# Frame2TTL_v2_1_1.net
KiCad netlist of a schematic drawn in EAGLE
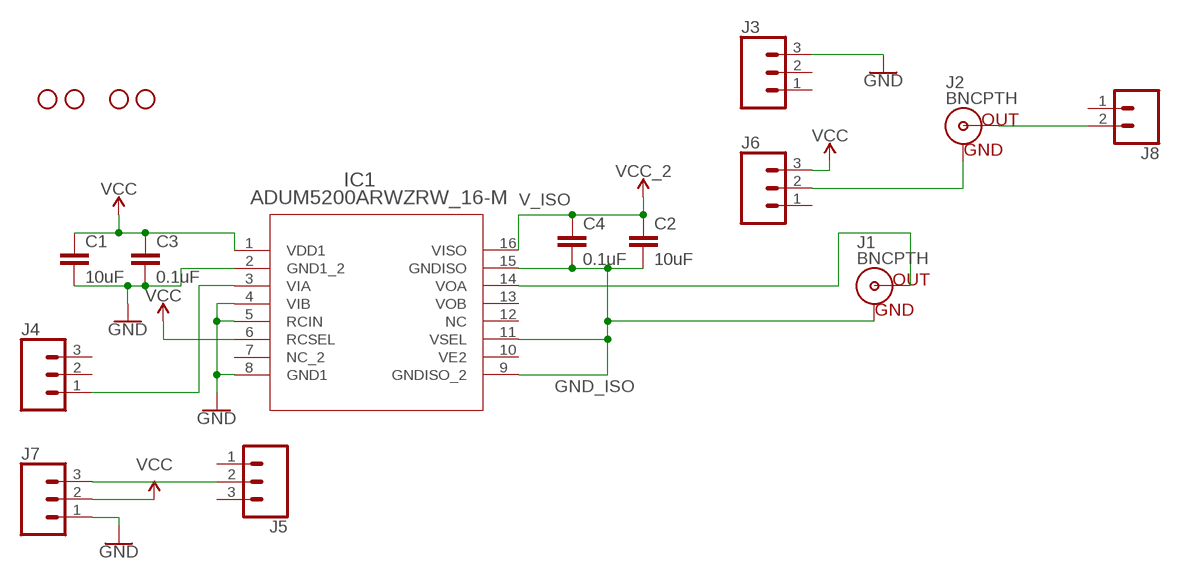
[diagram p0: schematic, sheet 1]

(export (version "E")
  (design (tool "Eeschema 10.0.6"))
  (components
    (comp (ref "C1")
      (value "10uF")
      (footprint "eagle-import:1206")
      (libsource (lib "eagle-import") (part "10UF-1206-6.3V-20%"))
    )
    (comp (ref "C2")
      (value "10uF")
      (footprint "eagle-import:1206")
      (libsource (lib "eagle-import") (part "10UF-1206-6.3V-20%"))
    )
    (comp (ref "C3")
      (value "0.1uF")
      (footprint "eagle-import:0805")
      (libsource (lib "eagle-import") (part "10UF-0805-10V-10%"))
    )
    (comp (ref "C4")
      (value "0.1uF")
      (footprint "eagle-import:0805")
      (libsource (lib "eagle-import") (part "10UF-0805-10V-10%"))
    )
    (comp (ref "H1")
      (value "STAND-OFF")
      (footprint "eagle-import:STAND-OFF")
      (libsource (lib "eagle-import") (part "STAND-OFF"))
    )
    (comp (ref "H2")
      (value "STAND-OFF")
      (footprint "eagle-import:STAND-OFF")
      (libsource (lib "eagle-import") (part "STAND-OFF"))
    )
    (comp (ref "H3")
      (value "STAND-OFF")
      (footprint "eagle-import:STAND-OFF")
      (libsource (lib "eagle-import") (part "STAND-OFF"))
    )
    (comp (ref "H4")
      (value "STAND-OFF")
      (footprint "eagle-import:STAND-OFF")
      (libsource (lib "eagle-import") (part "STAND-OFF"))
    )
    (comp (ref "IC1")
      (value "ADUM5200ARWZRW_16-M")
      (footprint "eagle-import:RW_16-M")
      (libsource (lib "eagle-import") (part "ADUM5200ARWZRW_16-M"))
    )
    (comp (ref "J1")
      (value "BNCPTH")
      (footprint "eagle-import:BNC")
      (libsource (lib "eagle-import") (part "BNCPTH"))
    )
    (comp (ref "J2")
      (value "BNCPTH")
      (footprint "eagle-import:BNC")
      (libsource (lib "eagle-import") (part "BNCPTH"))
    )
    (comp (ref "J3")
      (value "CONN_03LOCK")
      (footprint "eagle-import:1X03_LOCK")
      (libsource (lib "eagle-import") (part "CONN_03LOCK"))
    )
    (comp (ref "J4")
      (value "CONN_03LOCK")
      (footprint "eagle-import:1X03_LOCK")
      (libsource (lib "eagle-import") (part "CONN_03LOCK"))
    )
    (comp (ref "J5")
      (value "CONN_03LOCK")
      (footprint "eagle-import:1X03_LOCK")
      (libsource (lib "eagle-import") (part "CONN_03LOCK"))
    )
    (comp (ref "J6")
      (value "CONN_03LOCK")
      (footprint "eagle-import:1X03_LOCK")
      (libsource (lib "eagle-import") (part "CONN_03LOCK"))
    )
    (comp (ref "J7")
      (value "CONN_03LOCK")
      (footprint "eagle-import:1X03_LOCK")
      (libsource (lib "eagle-import") (part "CONN_03LOCK"))
    )
    (comp (ref "J8")
      (value "CONN_02")
      (footprint "eagle-import:1X02")
      (libsource (lib "eagle-import") (part "CONN_02"))
    )
  )
  (nets
    (net (code "1") (name "/GND_ISO") (class "Default")
      (node (ref "C2") (pin "2") (pinfunction "2_2") (pintype "passive"))
      (node (ref "C4") (pin "2") (pinfunction "2_2") (pintype "passive"))
      (node (ref "IC1") (pin "11") (pinfunction "VSEL_11") (pintype "passive"))
      (node (ref "IC1") (pin "15") (pinfunction "GNDISO_15") (pintype "passive"))
      (node (ref "IC1") (pin "9") (pinfunction "GNDISO_2_9") (pintype "passive"))
      (node (ref "J1") (pin "GND") (pinfunction "GND_GND") (pintype "bidirectional"))
    )
    (net (code "2") (name "GND") (class "Default")
      (node (ref "C1") (pin "2") (pinfunction "2_2") (pintype "passive"))
      (node (ref "C3") (pin "2") (pinfunction "2_2") (pintype "passive"))
      (node (ref "IC1") (pin "2") (pinfunction "GND1_2_2") (pintype "passive"))
      (node (ref "IC1") (pin "4") (pinfunction "VIB_4") (pintype "passive"))
      (node (ref "IC1") (pin "5") (pinfunction "RCIN_5") (pintype "passive"))
      (node (ref "IC1") (pin "8") (pinfunction "GND1_8") (pintype "passive"))
      (node (ref "J3") (pin "3") (pinfunction "3_3") (pintype "passive"))
      (node (ref "J7") (pin "1") (pinfunction "1_1") (pintype "passive"))
    )
    (net (code "3") (name "Net-(IC1-VIA)") (class "Default")
      (node (ref "IC1") (pin "3") (pinfunction "VIA_3") (pintype "passive"))
      (node (ref "J4") (pin "1") (pinfunction "1_1") (pintype "passive"))
    )
    (net (code "4") (name "Net-(IC1-VOA)") (class "Default")
      (node (ref "IC1") (pin "14") (pinfunction "VOA_14") (pintype "passive"))
      (node (ref "J1") (pin "S") (pinfunction "OUT_S") (pintype "bidirectional"))
    )
    (net (code "5") (name "Net-(J2-OUT)") (class "Default")
      (node (ref "J2") (pin "S") (pinfunction "OUT_S") (pintype "bidirectional"))
      (node (ref "J8") (pin "2") (pinfunction "2_2") (pintype "passive"))
    )
    (net (code "6") (name "Net-(J2-PadGND)") (class "Default")
      (node (ref "J2") (pin "GND") (pinfunction "GND_GND") (pintype "bidirectional"))
      (node (ref "J6") (pin "2") (pinfunction "2_2") (pintype "passive"))
    )
    (net (code "7") (name "Net-(J5-Pad2)") (class "Default")
      (node (ref "J5") (pin "2") (pinfunction "2_2") (pintype "passive"))
      (node (ref "J7") (pin "3") (pinfunction "3_3") (pintype "passive"))
    )
    (net (code "8") (name "VCC") (class "Default")
      (node (ref "C1") (pin "1") (pinfunction "1_1") (pintype "passive"))
      (node (ref "C3") (pin "1") (pinfunction "1_1") (pintype "passive"))
      (node (ref "IC1") (pin "1") (pinfunction "VDD1_1") (pintype "passive"))
      (node (ref "IC1") (pin "6") (pinfunction "RCSEL_6") (pintype "passive"))
      (node (ref "J6") (pin "3") (pinfunction "3_3") (pintype "passive"))
      (node (ref "J7") (pin "2") (pinfunction "2_2") (pintype "passive"))
    )
    (net (code "9") (name "VCC_2") (class "Default")
      (node (ref "C2") (pin "1") (pinfunction "1_1") (pintype "passive"))
      (node (ref "C4") (pin "1") (pinfunction "1_1") (pintype "passive"))
      (node (ref "IC1") (pin "16") (pinfunction "VISO_16") (pintype "passive"))
    )
    (net (code "10") (name "unconnected-(IC1-NC-Pad12)") (class "Default")
      (node (ref "IC1") (pin "12") (pinfunction "NC_12") (pintype "passive"))
    )
    (net (code "11") (name "unconnected-(IC1-NC_2-Pad7)") (class "Default")
      (node (ref "IC1") (pin "7") (pinfunction "NC_2_7") (pintype "passive"))
    )
    (net (code "12") (name "unconnected-(IC1-VE2-Pad10)") (class "Default")
      (node (ref "IC1") (pin "10") (pinfunction "VE2_10") (pintype "passive"))
    )
    (net (code "13") (name "unconnected-(IC1-VOB-Pad13)") (class "Default")
      (node (ref "IC1") (pin "13") (pinfunction "VOB_13") (pintype "passive"))
    )
    (net (code "14") (name "unconnected-(J3-Pad1)") (class "Default")
      (node (ref "J3") (pin "1") (pinfunction "1_1") (pintype "passive"))
    )
    (net (code "15") (name "unconnected-(J3-Pad2)") (class "Default")
      (node (ref "J3") (pin "2") (pinfunction "2_2") (pintype "passive"))
    )
    (net (code "16") (name "unconnected-(J4-Pad2)") (class "Default")
      (node (ref "J4") (pin "2") (pinfunction "2_2") (pintype "passive"))
    )
    (net (code "17") (name "unconnected-(J4-Pad3)") (class "Default")
      (node (ref "J4") (pin "3") (pinfunction "3_3") (pintype "passive"))
    )
    (net (code "18") (name "unconnected-(J5-Pad1)") (class "Default")
      (node (ref "J5") (pin "1") (pinfunction "1_1") (pintype "passive"))
    )
    (net (code "19") (name "unconnected-(J5-Pad3)") (class "Default")
      (node (ref "J5") (pin "3") (pinfunction "3_3") (pintype "passive"))
    )
    (net (code "20") (name "unconnected-(J6-Pad1)") (class "Default")
      (node (ref "J6") (pin "1") (pinfunction "1_1") (pintype "passive"))
    )
    (net (code "21") (name "unconnected-(J8-Pad1)") (class "Default")
      (node (ref "J8") (pin "1") (pinfunction "1_1") (pintype "passive"))
    )
  )
)
